# NAND.net
KiCad netlist of a schematic drawn in Altium Designer
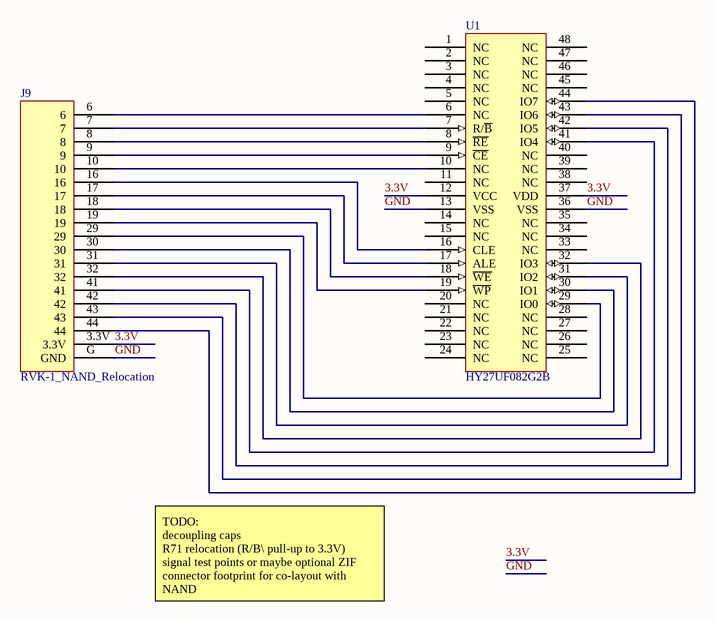
[diagram p0: NAND.SchDoc]

(export (version "E")
  (design (tool "Eeschema 10.0.6"))
  (components
    (comp (ref "J9")
      (value "RVK-1_NAND_Relocation")
      (footprint "RVK-1_NAND_Vias")
      (libsource (lib "WiirdFlex") (part "RVK-1_NAND_Relocation"))
    )
    (comp (ref "U1")
      (value "HY27UF082G2B")
      (footprint "TSSOP50P2000X120-48N")
      (description "NAND flash chip used on WII")
      (libsource (lib "WiirdFlex") (part "HY27UF082G2B"))
    )
  )
  (nets
    (net (code "1") (name "/3.3V") (class "Default")
      (node (ref "J9") (pin "3.3V") (pinfunction "3.3V_3.3V") (pintype "passive"))
      (node (ref "U1") (pin "12") (pinfunction "VCC_12") (pintype "power_in"))
      (node (ref "U1") (pin "37") (pinfunction "VDD_37") (pintype "power_in"))
    )
    (net (code "2") (name "/GND") (class "Default")
      (node (ref "J9") (pin "G") (pinfunction "GND_G") (pintype "passive"))
      (node (ref "U1") (pin "13") (pinfunction "VSS_13") (pintype "power_in"))
      (node (ref "U1") (pin "36") (pinfunction "VSS_36") (pintype "power_in"))
    )
    (net (code "3") (name "Net-(J9-Pad6)") (class "Default")
      (node (ref "J9") (pin "6") (pinfunction "6_6") (pintype "passive"))
      (node (ref "U1") (pin "6") (pinfunction "NC_6") (pintype "passive"))
    )
    (net (code "4") (name "Net-(J9-Pad10)") (class "Default")
      (node (ref "J9") (pin "10") (pinfunction "10_10") (pintype "passive"))
      (node (ref "U1") (pin "10") (pinfunction "NC_10") (pintype "passive"))
    )
    (net (code "5") (name "Net-(U1-ALE)") (class "Default")
      (node (ref "J9") (pin "17") (pinfunction "17_17") (pintype "passive"))
      (node (ref "U1") (pin "17") (pinfunction "ALE_17") (pintype "input"))
    )
    (net (code "6") (name "Net-(U1-CLE)") (class "Default")
      (node (ref "J9") (pin "16") (pinfunction "16_16") (pintype "passive"))
      (node (ref "U1") (pin "16") (pinfunction "CLE_16") (pintype "input"))
    )
    (net (code "7") (name "Net-(U1-IO0)") (class "Default")
      (node (ref "J9") (pin "29") (pinfunction "29_29") (pintype "passive"))
      (node (ref "U1") (pin "29") (pinfunction "IO0_29") (pintype "bidirectional"))
    )
    (net (code "8") (name "Net-(U1-IO1)") (class "Default")
      (node (ref "J9") (pin "30") (pinfunction "30_30") (pintype "passive"))
      (node (ref "U1") (pin "30") (pinfunction "IO1_30") (pintype "bidirectional"))
    )
    (net (code "9") (name "Net-(U1-IO2)") (class "Default")
      (node (ref "J9") (pin "31") (pinfunction "31_31") (pintype "passive"))
      (node (ref "U1") (pin "31") (pinfunction "IO2_31") (pintype "bidirectional"))
    )
    (net (code "10") (name "Net-(U1-IO3)") (class "Default")
      (node (ref "J9") (pin "32") (pinfunction "32_32") (pintype "passive"))
      (node (ref "U1") (pin "32") (pinfunction "IO3_32") (pintype "bidirectional"))
    )
    (net (code "11") (name "Net-(U1-IO4)") (class "Default")
      (node (ref "J9") (pin "41") (pinfunction "41_41") (pintype "passive"))
      (node (ref "U1") (pin "41") (pinfunction "IO4_41") (pintype "bidirectional"))
    )
    (net (code "12") (name "Net-(U1-IO5)") (class "Default")
      (node (ref "J9") (pin "42") (pinfunction "42_42") (pintype "passive"))
      (node (ref "U1") (pin "42") (pinfunction "IO5_42") (pintype "bidirectional"))
    )
    (net (code "13") (name "Net-(U1-IO6)") (class "Default")
      (node (ref "J9") (pin "43") (pinfunction "43_43") (pintype "passive"))
      (node (ref "U1") (pin "43") (pinfunction "IO6_43") (pintype "bidirectional"))
    )
    (net (code "14") (name "Net-(U1-IO7)") (class "Default")
      (node (ref "J9") (pin "44") (pinfunction "44_44") (pintype "passive"))
      (node (ref "U1") (pin "44") (pinfunction "IO7_44") (pintype "bidirectional"))
    )
    (net (code "15") (name "Net-(U1-R{slash}~{B})") (class "Default")
      (node (ref "J9") (pin "7") (pinfunction "7_7") (pintype "passive"))
      (node (ref "U1") (pin "7") (pinfunction "R/~{B}_7") (pintype "input"))
    )
    (net (code "16") (name "Net-(U1-~{CE})") (class "Default")
      (node (ref "J9") (pin "9") (pinfunction "9_9") (pintype "passive"))
      (node (ref "U1") (pin "9") (pinfunction "~{CE}_9") (pintype "input"))
    )
    (net (code "17") (name "Net-(U1-~{RE})") (class "Default")
      (node (ref "J9") (pin "8") (pinfunction "8_8") (pintype "passive"))
      (node (ref "U1") (pin "8") (pinfunction "~{RE}_8") (pintype "input"))
    )
    (net (code "18") (name "Net-(U1-~{WE})") (class "Default")
      (node (ref "J9") (pin "18") (pinfunction "18_18") (pintype "passive"))
      (node (ref "U1") (pin "18") (pinfunction "~{WE}_18") (pintype "input"))
    )
    (net (code "19") (name "Net-(U1-~{WP})") (class "Default")
      (node (ref "J9") (pin "19") (pinfunction "19_19") (pintype "passive"))
      (node (ref "U1") (pin "19") (pinfunction "~{WP}_19") (pintype "input"))
    )
    (net (code "20") (name "unconnected-(U1-NC-Pad1)") (class "Default")
      (node (ref "U1") (pin "1") (pinfunction "NC_1") (pintype "passive"))
    )
    (net (code "21") (name "unconnected-(U1-NC-Pad2)") (class "Default")
      (node (ref "U1") (pin "2") (pinfunction "NC_2") (pintype "passive"))
    )
    (net (code "22") (name "unconnected-(U1-NC-Pad3)") (class "Default")
      (node (ref "U1") (pin "3") (pinfunction "NC_3") (pintype "passive"))
    )
    (net (code "23") (name "unconnected-(U1-NC-Pad4)") (class "Default")
      (node (ref "U1") (pin "4") (pinfunction "NC_4") (pintype "passive"))
    )
    (net (code "24") (name "unconnected-(U1-NC-Pad5)") (class "Default")
      (node (ref "U1") (pin "5") (pinfunction "NC_5") (pintype "passive"))
    )
    (net (code "25") (name "unconnected-(U1-NC-Pad11)") (class "Default")
      (node (ref "U1") (pin "11") (pinfunction "NC_11") (pintype "passive"))
    )
    (net (code "26") (name "unconnected-(U1-NC-Pad14)") (class "Default")
      (node (ref "U1") (pin "14") (pinfunction "NC_14") (pintype "passive"))
    )
    (net (code "27") (name "unconnected-(U1-NC-Pad15)") (class "Default")
      (node (ref "U1") (pin "15") (pinfunction "NC_15") (pintype "passive"))
    )
    (net (code "28") (name "unconnected-(U1-NC-Pad20)") (class "Default")
      (node (ref "U1") (pin "20") (pinfunction "NC_20") (pintype "passive"))
    )
    (net (code "29") (name "unconnected-(U1-NC-Pad21)") (class "Default")
      (node (ref "U1") (pin "21") (pinfunction "NC_21") (pintype "passive"))
    )
    (net (code "30") (name "unconnected-(U1-NC-Pad22)") (class "Default")
      (node (ref "U1") (pin "22") (pinfunction "NC_22") (pintype "passive"))
    )
    (net (code "31") (name "unconnected-(U1-NC-Pad23)") (class "Default")
      (node (ref "U1") (pin "23") (pinfunction "NC_23") (pintype "passive"))
    )
    (net (code "32") (name "unconnected-(U1-NC-Pad24)") (class "Default")
      (node (ref "U1") (pin "24") (pinfunction "NC_24") (pintype "passive"))
    )
    (net (code "33") (name "unconnected-(U1-NC-Pad25)") (class "Default")
      (node (ref "U1") (pin "25") (pinfunction "NC_25") (pintype "passive"))
    )
    (net (code "34") (name "unconnected-(U1-NC-Pad26)") (class "Default")
      (node (ref "U1") (pin "26") (pinfunction "NC_26") (pintype "passive"))
    )
    (net (code "35") (name "unconnected-(U1-NC-Pad27)") (class "Default")
      (node (ref "U1") (pin "27") (pinfunction "NC_27") (pintype "passive"))
    )
    (net (code "36") (name "unconnected-(U1-NC-Pad28)") (class "Default")
      (node (ref "U1") (pin "28") (pinfunction "NC_28") (pintype "passive"))
    )
    (net (code "37") (name "unconnected-(U1-NC-Pad33)") (class "Default")
      (node (ref "U1") (pin "33") (pinfunction "NC_33") (pintype "passive"))
    )
    (net (code "38") (name "unconnected-(U1-NC-Pad34)") (class "Default")
      (node (ref "U1") (pin "34") (pinfunction "NC_34") (pintype "passive"))
    )
    (net (code "39") (name "unconnected-(U1-NC-Pad35)") (class "Default")
      (node (ref "U1") (pin "35") (pinfunction "NC_35") (pintype "passive"))
    )
    (net (code "40") (name "unconnected-(U1-NC-Pad38)") (class "Default")
      (node (ref "U1") (pin "38") (pinfunction "NC_38") (pintype "passive"))
    )
    (net (code "41") (name "unconnected-(U1-NC-Pad39)") (class "Default")
      (node (ref "U1") (pin "39") (pinfunction "NC_39") (pintype "passive"))
    )
    (net (code "42") (name "unconnected-(U1-NC-Pad40)") (class "Default")
      (node (ref "U1") (pin "40") (pinfunction "NC_40") (pintype "passive"))
    )
    (net (code "43") (name "unconnected-(U1-NC-Pad45)") (class "Default")
      (node (ref "U1") (pin "45") (pinfunction "NC_45") (pintype "passive"))
    )
    (net (code "44") (name "unconnected-(U1-NC-Pad46)") (class "Default")
      (node (ref "U1") (pin "46") (pinfunction "NC_46") (pintype "passive"))
    )
    (net (code "45") (name "unconnected-(U1-NC-Pad47)") (class "Default")
      (node (ref "U1") (pin "47") (pinfunction "NC_47") (pintype "passive"))
    )
    (net (code "46") (name "unconnected-(U1-NC-Pad48)") (class "Default")
      (node (ref "U1") (pin "48") (pinfunction "NC_48") (pintype "passive"))
    )
  )
)
